# hw2.net
KiCad netlist of a schematic drawn in EAGLE
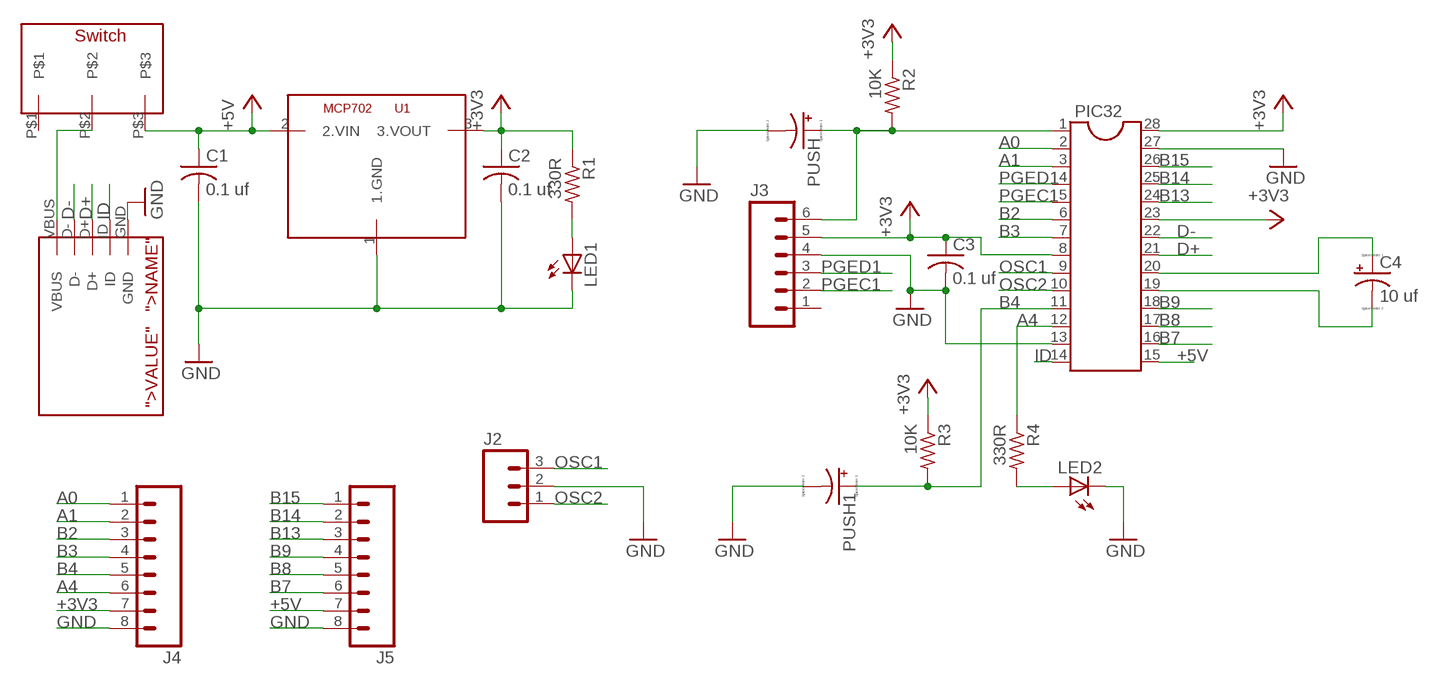
[diagram p0: schematic, sheet 1]

(export (version "E")
  (design (tool "Eeschema 10.0.6"))
  (components
    (comp (ref "C1")
      (value "0.1 uf")
      (footprint "eagle-import:C025-024X044")
      (libsource (lib "eagle-import") (part "C-US025-024X044"))
    )
    (comp (ref "C2")
      (value "0.1 uf")
      (footprint "eagle-import:C025-024X044")
      (libsource (lib "eagle-import") (part "C-US025-024X044"))
    )
    (comp (ref "C3")
      (value "0.1 uf")
      (footprint "eagle-import:C025-024X044")
      (libsource (lib "eagle-import") (part "C-US025-024X044"))
    )
    (comp (ref "C4")
      (value "10 uf")
      (footprint "eagle-import:TT2D4")
      (libsource (lib "eagle-import") (part "CPOL-USTT2D4"))
    )
    (comp (ref "J2")
      (value "M03LOCK")
      (footprint "eagle-import:1X03_LOCK")
      (libsource (lib "eagle-import") (part "M03LOCK"))
    )
    (comp (ref "J3")
      (value "M06NO_SILK_YES_STOP")
      (footprint "eagle-import:1X06_NO_SILK_YES_STOP")
      (libsource (lib "eagle-import") (part "M06NO_SILK_YES_STOP"))
    )
    (comp (ref "J4")
      (value "M08NO_SILK")
      (footprint "eagle-import:1X08_PIN1_NO_SILK")
      (libsource (lib "eagle-import") (part "M08NO_SILK"))
    )
    (comp (ref "J5")
      (value "M08NO_SILK")
      (footprint "eagle-import:1X08_PIN1_NO_SILK")
      (libsource (lib "eagle-import") (part "M08NO_SILK"))
    )
    (comp (ref "LED1")
      (value "LED3MM")
      (footprint "eagle-import:LED3MM")
      (libsource (lib "eagle-import") (part "LED3MM"))
    )
    (comp (ref "LED2")
      (value "LED3MM")
      (footprint "eagle-import:LED3MM")
      (libsource (lib "eagle-import") (part "LED3MM"))
    )
    (comp (ref "PIC32")
      (value "DIL28-3")
      (footprint "eagle-import:DIL28-3")
      (libsource (lib "eagle-import") (part "DIL28-3"))
    )
    (comp (ref "PUSH")
      (value "CPOL-USTAP5-60")
      (footprint "eagle-import:TAP5-60")
      (libsource (lib "eagle-import") (part "CPOL-USTAP5-60"))
    )
    (comp (ref "PUSH1")
      (value "CPOL-USTAP5-60")
      (footprint "eagle-import:TAP5-60")
      (libsource (lib "eagle-import") (part "CPOL-USTAP5-60"))
    )
    (comp (ref "R1")
      (value "330R")
      (footprint "eagle-import:0204_7")
      (libsource (lib "eagle-import") (part "R-US_0204/7"))
    )
    (comp (ref "R2")
      (value "10K")
      (footprint "eagle-import:0204_7")
      (libsource (lib "eagle-import") (part "R-US_0204/7"))
    )
    (comp (ref "R3")
      (value "10K")
      (footprint "eagle-import:0204_7")
      (libsource (lib "eagle-import") (part "R-US_0204/7"))
    )
    (comp (ref "R4")
      (value "330R")
      (footprint "eagle-import:0204_7")
      (libsource (lib "eagle-import") (part "R-US_0204/7"))
    )
    (comp (ref "U$1")
      (value "SWITCH")
      (footprint "eagle-import:SWITCH")
      (libsource (lib "eagle-import") (part "SWITCH"))
    )
    (comp (ref "U$2")
      (value "MCP1702")
      (footprint "eagle-import:TO92")
      (libsource (lib "eagle-import") (part "MCP1702"))
    )
    (comp (ref "U$3")
      (value "USBNEW")
      (footprint "eagle-import:USB-MB-H")
      (libsource (lib "eagle-import") (part "USBNEW"))
    )
  )
  (nets
    (net (code "1") (name "+3V3") (class "Default")
      (node (ref "C2") (pin "1") (pinfunction "1_1") (pintype "passive"))
      (node (ref "C3") (pin "1") (pinfunction "1_1") (pintype "passive"))
      (node (ref "J3") (pin "5") (pinfunction "VDD_5") (pintype "passive"))
      (node (ref "J4") (pin "7") (pinfunction "7_7") (pintype "passive"))
      (node (ref "PIC32") (pin "23") (pinfunction "23_23") (pintype "passive"))
      (node (ref "PIC32") (pin "28") (pinfunction "28_28") (pintype "passive"))
      (node (ref "PIC32") (pin "8") (pinfunction "8_8") (pintype "passive"))
      (node (ref "R1") (pin "1") (pinfunction "1_1") (pintype "passive"))
      (node (ref "R2") (pin "1") (pinfunction "1_1") (pintype "passive"))
      (node (ref "R3") (pin "1") (pinfunction "1_1") (pintype "passive"))
      (node (ref "U$2") (pin "3") (pinfunction "3.VOUT_3") (pintype "bidirectional"))
    )
    (net (code "2") (name "+5V") (class "Default")
      (node (ref "C1") (pin "1") (pinfunction "1_1") (pintype "passive"))
      (node (ref "J5") (pin "7") (pinfunction "7_7") (pintype "passive"))
      (node (ref "PIC32") (pin "15") (pinfunction "15_15") (pintype "passive"))
      (node (ref "U$1") (pin "P$3") (pinfunction "P$3_P$3") (pintype "bidirectional"))
      (node (ref "U$2") (pin "2") (pinfunction "2.VIN_2") (pintype "bidirectional"))
    )
    (net (code "3") (name "/A0") (class "Default")
      (node (ref "J4") (pin "1") (pinfunction "1_1") (pintype "passive"))
      (node (ref "PIC32") (pin "2") (pinfunction "2_2") (pintype "passive"))
    )
    (net (code "4") (name "/A1") (class "Default")
      (node (ref "J4") (pin "2") (pinfunction "2_2") (pintype "passive"))
      (node (ref "PIC32") (pin "3") (pinfunction "3_3") (pintype "passive"))
    )
    (net (code "5") (name "/A4") (class "Default")
      (node (ref "J4") (pin "6") (pinfunction "6_6") (pintype "passive"))
      (node (ref "PIC32") (pin "12") (pinfunction "12_12") (pintype "passive"))
      (node (ref "R4") (pin "1") (pinfunction "1_1") (pintype "passive"))
    )
    (net (code "6") (name "/B2") (class "Default")
      (node (ref "J4") (pin "3") (pinfunction "3_3") (pintype "passive"))
      (node (ref "PIC32") (pin "6") (pinfunction "6_6") (pintype "passive"))
    )
    (net (code "7") (name "/B3") (class "Default")
      (node (ref "J4") (pin "4") (pinfunction "4_4") (pintype "passive"))
      (node (ref "PIC32") (pin "7") (pinfunction "7_7") (pintype "passive"))
    )
    (net (code "8") (name "/B4") (class "Default")
      (node (ref "J4") (pin "5") (pinfunction "5_5") (pintype "passive"))
      (node (ref "PIC32") (pin "11") (pinfunction "11_11") (pintype "passive"))
      (node (ref "PUSH1") (pin "+") (pinfunction "+_+") (pintype "passive"))
      (node (ref "R3") (pin "2") (pinfunction "2_2") (pintype "passive"))
    )
    (net (code "9") (name "/B7") (class "Default")
      (node (ref "J5") (pin "6") (pinfunction "6_6") (pintype "passive"))
      (node (ref "PIC32") (pin "16") (pinfunction "16_16") (pintype "passive"))
    )
    (net (code "10") (name "/B8") (class "Default")
      (node (ref "J5") (pin "5") (pinfunction "5_5") (pintype "passive"))
      (node (ref "PIC32") (pin "17") (pinfunction "17_17") (pintype "passive"))
    )
    (net (code "11") (name "/B9") (class "Default")
      (node (ref "J5") (pin "4") (pinfunction "4_4") (pintype "passive"))
      (node (ref "PIC32") (pin "18") (pinfunction "18_18") (pintype "passive"))
    )
    (net (code "12") (name "/B13") (class "Default")
      (node (ref "J5") (pin "3") (pinfunction "3_3") (pintype "passive"))
      (node (ref "PIC32") (pin "24") (pinfunction "24_24") (pintype "passive"))
    )
    (net (code "13") (name "/B14") (class "Default")
      (node (ref "J5") (pin "2") (pinfunction "2_2") (pintype "passive"))
      (node (ref "PIC32") (pin "25") (pinfunction "25_25") (pintype "passive"))
    )
    (net (code "14") (name "/B15") (class "Default")
      (node (ref "J5") (pin "1") (pinfunction "1_1") (pintype "passive"))
      (node (ref "PIC32") (pin "26") (pinfunction "26_26") (pintype "passive"))
    )
    (net (code "15") (name "/D+") (class "Default")
      (node (ref "PIC32") (pin "21") (pinfunction "21_21") (pintype "passive"))
      (node (ref "U$3") (pin "D+") (pinfunction "D+_D+") (pintype "bidirectional"))
    )
    (net (code "16") (name "/D-") (class "Default")
      (node (ref "PIC32") (pin "22") (pinfunction "22_22") (pintype "passive"))
      (node (ref "U$3") (pin "D-") (pinfunction "D-_D-") (pintype "bidirectional"))
    )
    (net (code "17") (name "/ID") (class "Default")
      (node (ref "PIC32") (pin "14") (pinfunction "14_14") (pintype "passive"))
      (node (ref "U$3") (pin "ID") (pinfunction "ID_ID") (pintype "bidirectional"))
    )
    (net (code "18") (name "/OSC1") (class "Default")
      (node (ref "J2") (pin "3") (pinfunction "3_3") (pintype "passive"))
      (node (ref "PIC32") (pin "9") (pinfunction "9_9") (pintype "passive"))
    )
    (net (code "19") (name "/OSC2") (class "Default")
      (node (ref "J2") (pin "1") (pinfunction "1_1") (pintype "passive"))
      (node (ref "PIC32") (pin "10") (pinfunction "10_10") (pintype "passive"))
    )
    (net (code "20") (name "/PGEC1") (class "Default")
      (node (ref "J3") (pin "2") (pinfunction "PGC_2") (pintype "passive"))
      (node (ref "PIC32") (pin "5") (pinfunction "5_5") (pintype "passive"))
    )
    (net (code "21") (name "/PGED1") (class "Default")
      (node (ref "J3") (pin "3") (pinfunction "PGD_3") (pintype "passive"))
      (node (ref "PIC32") (pin "4") (pinfunction "4_4") (pintype "passive"))
    )
    (net (code "22") (name "GND") (class "Default")
      (node (ref "C1") (pin "2") (pinfunction "2_2") (pintype "passive"))
      (node (ref "C2") (pin "2") (pinfunction "2_2") (pintype "passive"))
      (node (ref "C3") (pin "2") (pinfunction "2_2") (pintype "passive"))
      (node (ref "J2") (pin "2") (pinfunction "2_2") (pintype "passive"))
      (node (ref "J3") (pin "4") (pinfunction "VSS_4") (pintype "passive"))
      (node (ref "J4") (pin "8") (pinfunction "8_8") (pintype "passive"))
      (node (ref "J5") (pin "8") (pinfunction "8_8") (pintype "passive"))
      (node (ref "LED1") (pin "K") (pinfunction "C_K") (pintype "passive"))
      (node (ref "LED2") (pin "K") (pinfunction "C_K") (pintype "passive"))
      (node (ref "PIC32") (pin "13") (pinfunction "13_13") (pintype "passive"))
      (node (ref "PIC32") (pin "27") (pinfunction "27_27") (pintype "passive"))
      (node (ref "PUSH") (pin "-") (pinfunction "-_-") (pintype "passive"))
      (node (ref "PUSH1") (pin "-") (pinfunction "-_-") (pintype "passive"))
      (node (ref "U$2") (pin "1") (pinfunction "1.GND_1") (pintype "bidirectional"))
      (node (ref "U$3") (pin "GND") (pinfunction "GND_GND") (pintype "bidirectional"))
    )
    (net (code "23") (name "Net-(C4-Pad+)") (class "Default")
      (node (ref "C4") (pin "+") (pinfunction "+_+") (pintype "passive"))
      (node (ref "PIC32") (pin "20") (pinfunction "20_20") (pintype "passive"))
    )
    (net (code "24") (name "Net-(C4-Pad-)") (class "Default")
      (node (ref "C4") (pin "-") (pinfunction "-_-") (pintype "passive"))
      (node (ref "PIC32") (pin "19") (pinfunction "19_19") (pintype "passive"))
    )
    (net (code "25") (name "Net-(J3-MCLB)") (class "Default")
      (node (ref "J3") (pin "6") (pinfunction "MCLB_6") (pintype "passive"))
      (node (ref "PIC32") (pin "1") (pinfunction "1_1") (pintype "passive"))
      (node (ref "PUSH") (pin "+") (pinfunction "+_+") (pintype "passive"))
      (node (ref "R2") (pin "2") (pinfunction "2_2") (pintype "passive"))
    )
    (net (code "26") (name "Net-(LED1-PadA)") (class "Default")
      (node (ref "LED1") (pin "A") (pinfunction "A_A") (pintype "passive"))
      (node (ref "R1") (pin "2") (pinfunction "2_2") (pintype "passive"))
    )
    (net (code "27") (name "Net-(LED2-PadA)") (class "Default")
      (node (ref "LED2") (pin "A") (pinfunction "A_A") (pintype "passive"))
      (node (ref "R4") (pin "2") (pinfunction "2_2") (pintype "passive"))
    )
    (net (code "28") (name "Net-(U$1-PadP$2)") (class "Default")
      (node (ref "U$1") (pin "P$2") (pinfunction "P$2_P$2") (pintype "bidirectional"))
      (node (ref "U$3") (pin "VBUS") (pinfunction "VBUS_VBUS") (pintype "bidirectional"))
    )
    (net (code "29") (name "unconnected-(J3-PGM-Pad1)") (class "Default")
      (node (ref "J3") (pin "1") (pinfunction "PGM_1") (pintype "passive"))
    )
    (net (code "30") (name "unconnected-(U$1-PadP$1)") (class "Default")
      (node (ref "U$1") (pin "P$1") (pinfunction "P$1_P$1") (pintype "bidirectional"))
    )
  )
)
